# QI-01.net
KiCad netlist of a schematic drawn in EAGLE
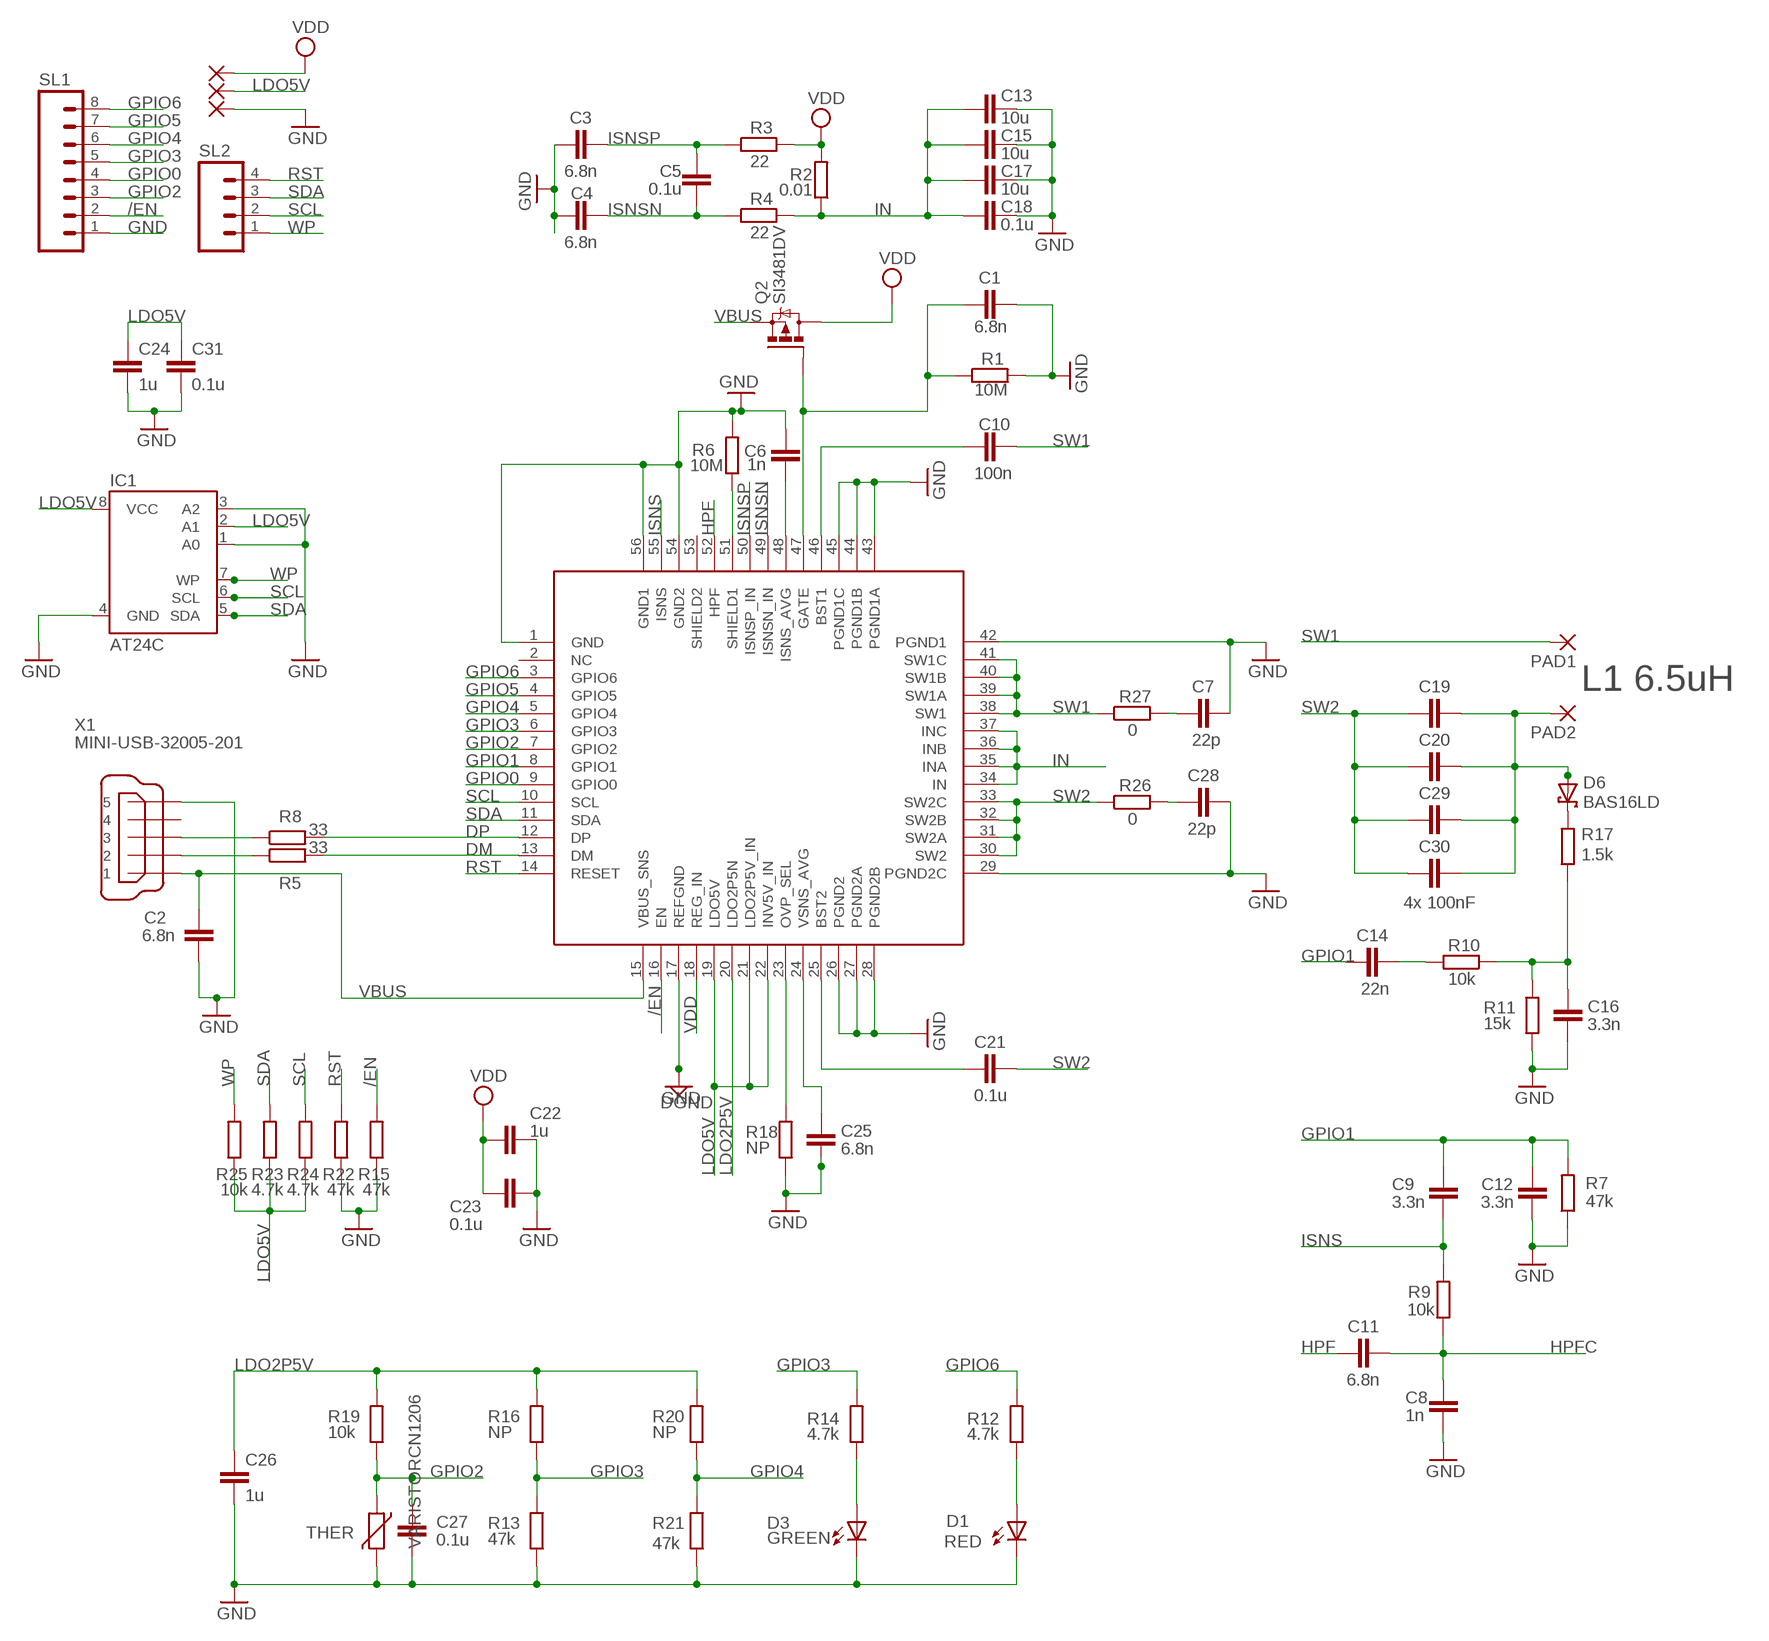
[diagram p0: schematic, sheet 1]

(export (version "E")
  (design (tool "Eeschema 10.0.6"))
  (components
    (comp (ref "C1")
      (value "6.8n")
      (footprint "eagle-import:C0402")
      (libsource (lib "eagle-import") (part "C-EUC0402"))
    )
    (comp (ref "C2")
      (value "6.8n")
      (footprint "eagle-import:C0402")
      (libsource (lib "eagle-import") (part "C-EUC0402"))
    )
    (comp (ref "C3")
      (value "6.8n")
      (footprint "eagle-import:C0402")
      (libsource (lib "eagle-import") (part "C-EUC0402"))
    )
    (comp (ref "C4")
      (value "6.8n")
      (footprint "eagle-import:C0402")
      (libsource (lib "eagle-import") (part "C-EUC0402"))
    )
    (comp (ref "C5")
      (value "0.1u")
      (footprint "eagle-import:C0402")
      (libsource (lib "eagle-import") (part "C-EUC0402"))
    )
    (comp (ref "C6")
      (value "1n")
      (footprint "eagle-import:C0402")
      (libsource (lib "eagle-import") (part "C-EUC0402"))
    )
    (comp (ref "C7")
      (value "22p")
      (footprint "eagle-import:C0402")
      (libsource (lib "eagle-import") (part "C-EUC0402"))
    )
    (comp (ref "C8")
      (value "1n")
      (footprint "eagle-import:C0402")
      (libsource (lib "eagle-import") (part "C-EUC0402"))
    )
    (comp (ref "C9")
      (value "3.3n")
      (footprint "eagle-import:C0402")
      (libsource (lib "eagle-import") (part "C-EUC0402"))
    )
    (comp (ref "C10")
      (value "100n")
      (footprint "eagle-import:C0402")
      (libsource (lib "eagle-import") (part "C-EUC0402"))
    )
    (comp (ref "C11")
      (value "6.8n")
      (footprint "eagle-import:C0402")
      (libsource (lib "eagle-import") (part "C-EUC0402"))
    )
    (comp (ref "C12")
      (value "3.3n")
      (footprint "eagle-import:C0402")
      (libsource (lib "eagle-import") (part "C-EUC0402"))
    )
    (comp (ref "C13")
      (value "10u")
      (footprint "eagle-import:C0805")
      (libsource (lib "eagle-import") (part "C-EUC0805"))
    )
    (comp (ref "C14")
      (value "22n")
      (footprint "eagle-import:C0402")
      (libsource (lib "eagle-import") (part "C-EUC0402"))
    )
    (comp (ref "C15")
      (value "10u")
      (footprint "eagle-import:C0805")
      (libsource (lib "eagle-import") (part "C-EUC0805"))
    )
    (comp (ref "C16")
      (value "3.3n")
      (footprint "eagle-import:C0402")
      (libsource (lib "eagle-import") (part "C-EUC0402"))
    )
    (comp (ref "C17")
      (value "10u")
      (footprint "eagle-import:C0805")
      (libsource (lib "eagle-import") (part "C-EUC0805"))
    )
    (comp (ref "C18")
      (value "0.1u")
      (footprint "eagle-import:C0402")
      (libsource (lib "eagle-import") (part "C-EUC0402"))
    )
    (comp (ref "C19")
      (value "100n")
      (footprint "eagle-import:C1206")
      (libsource (lib "eagle-import") (part "C-EUC1206"))
    )
    (comp (ref "C20")
      (value "100n")
      (footprint "eagle-import:C1206")
      (libsource (lib "eagle-import") (part "C-EUC1206"))
    )
    (comp (ref "C21")
      (value "0.1u")
      (footprint "eagle-import:C0402")
      (libsource (lib "eagle-import") (part "C-EUC0402"))
    )
    (comp (ref "C22")
      (value "1u")
      (footprint "eagle-import:C0402")
      (libsource (lib "eagle-import") (part "C-EUC0402"))
    )
    (comp (ref "C23")
      (value "0.1u")
      (footprint "eagle-import:C0402")
      (libsource (lib "eagle-import") (part "C-EUC0402"))
    )
    (comp (ref "C24")
      (value "1u")
      (footprint "eagle-import:C0402")
      (libsource (lib "eagle-import") (part "C-EUC0402"))
    )
    (comp (ref "C25")
      (value "6.8n")
      (footprint "eagle-import:C0402")
      (libsource (lib "eagle-import") (part "C-EUC0402"))
    )
    (comp (ref "C26")
      (value "1u")
      (footprint "eagle-import:C0402")
      (libsource (lib "eagle-import") (part "C-EUC0402"))
    )
    (comp (ref "C27")
      (value "0.1u")
      (footprint "eagle-import:C0402")
      (libsource (lib "eagle-import") (part "C-EUC0402"))
    )
    (comp (ref "C28")
      (value "22p")
      (footprint "eagle-import:C0402")
      (libsource (lib "eagle-import") (part "C-EUC0402"))
    )
    (comp (ref "C29")
      (value "100n")
      (footprint "eagle-import:C1206")
      (libsource (lib "eagle-import") (part "C-EUC1206"))
    )
    (comp (ref "C30")
      (value "100n")
      (footprint "eagle-import:C1206")
      (libsource (lib "eagle-import") (part "C-EUC1206"))
    )
    (comp (ref "C31")
      (value "0.1u")
      (footprint "eagle-import:C0402")
      (libsource (lib "eagle-import") (part "C-EUC0402"))
    )
    (comp (ref "D1")
      (value "RED")
      (footprint "eagle-import:SML0603")
      (libsource (lib "eagle-import") (part "LEDSML0603"))
    )
    (comp (ref "D3")
      (value "GREEN")
      (footprint "eagle-import:SML0603")
      (libsource (lib "eagle-import") (part "LEDSML0603"))
    )
    (comp (ref "D6")
      (value "BAS16LD")
      (footprint "eagle-import:SMB")
      (libsource (lib "eagle-import") (part "SCHOTTKY-DIODESMD"))
    )
    (comp (ref "IC1")
      (value "AT24C")
      (footprint "eagle-import:TSSOP8")
      (fields (field (name "SPICEPREFIX") "X"))
      (libsource (lib "eagle-import") (part "AT24C"))
    )
    (comp (ref "PAD1")
      (value "2,54/1,0")
      (footprint "eagle-import:2,54_1,0")
      (libsource (lib "eagle-import") (part "2,54/1,0"))
    )
    (comp (ref "PAD2")
      (value "2,54/1,0")
      (footprint "eagle-import:2,54_1,0")
      (libsource (lib "eagle-import") (part "2,54/1,0"))
    )
    (comp (ref "PAD3")
      (value "2,15/1,0")
      (footprint "eagle-import:2,15_1,0")
      (libsource (lib "eagle-import") (part "2,15/1,0"))
    )
    (comp (ref "PAD4")
      (value "2,15/1,0")
      (footprint "eagle-import:2,15_1,0")
      (libsource (lib "eagle-import") (part "2,15/1,0"))
    )
    (comp (ref "PAD5")
      (value "2,15/1,0")
      (footprint "eagle-import:2,15_1,0")
      (libsource (lib "eagle-import") (part "2,15/1,0"))
    )
    (comp (ref "Q2")
      (value "SI3481DV")
      (footprint "eagle-import:TSOP-6.PAC")
      (libsource (lib "eagle-import") (part "SI3481DV"))
    )
    (comp (ref "R1")
      (value "10M")
      (footprint "eagle-import:R0402")
      (libsource (lib "eagle-import") (part "R-EU_R0402"))
    )
    (comp (ref "R2")
      (value "0.01")
      (footprint "eagle-import:R0805")
      (libsource (lib "eagle-import") (part "R-EU_R0805"))
    )
    (comp (ref "R3")
      (value "22")
      (footprint "eagle-import:R0402")
      (libsource (lib "eagle-import") (part "R-EU_R0402"))
    )
    (comp (ref "R4")
      (value "22")
      (footprint "eagle-import:R0402")
      (libsource (lib "eagle-import") (part "R-EU_R0402"))
    )
    (comp (ref "R5")
      (value "33")
      (footprint "eagle-import:R0402")
      (libsource (lib "eagle-import") (part "R-EU_R0402"))
    )
    (comp (ref "R6")
      (value "10M")
      (footprint "eagle-import:R0402")
      (libsource (lib "eagle-import") (part "R-EU_R0402"))
    )
    (comp (ref "R7")
      (value "47k")
      (footprint "eagle-import:R0402")
      (libsource (lib "eagle-import") (part "R-EU_R0402"))
    )
    (comp (ref "R8")
      (value "33")
      (footprint "eagle-import:R0402")
      (libsource (lib "eagle-import") (part "R-EU_R0402"))
    )
    (comp (ref "R9")
      (value "10k")
      (footprint "eagle-import:R0402")
      (libsource (lib "eagle-import") (part "R-EU_R0402"))
    )
    (comp (ref "R10")
      (value "10k")
      (footprint "eagle-import:R0402")
      (libsource (lib "eagle-import") (part "R-EU_R0402"))
    )
    (comp (ref "R11")
      (value "15k")
      (footprint "eagle-import:R0402")
      (libsource (lib "eagle-import") (part "R-EU_R0402"))
    )
    (comp (ref "R12")
      (value "4.7k")
      (footprint "eagle-import:R0402")
      (libsource (lib "eagle-import") (part "R-EU_R0402"))
    )
    (comp (ref "R13")
      (value "47k")
      (footprint "eagle-import:R0603")
      (libsource (lib "eagle-import") (part "R-EU_R0603"))
    )
    (comp (ref "R14")
      (value "4.7k")
      (footprint "eagle-import:R0402")
      (libsource (lib "eagle-import") (part "R-EU_R0402"))
    )
    (comp (ref "R15")
      (value "47k")
      (footprint "eagle-import:R0603")
      (libsource (lib "eagle-import") (part "R-EU_R0603"))
    )
    (comp (ref "R16")
      (value "NP")
      (footprint "eagle-import:R0402")
      (libsource (lib "eagle-import") (part "R-EU_R0402"))
    )
    (comp (ref "R17")
      (value "1.5k")
      (footprint "eagle-import:R0402")
      (libsource (lib "eagle-import") (part "R-EU_R0402"))
    )
    (comp (ref "R18")
      (value "NP")
      (footprint "eagle-import:R0402")
      (libsource (lib "eagle-import") (part "R-EU_R0402"))
    )
    (comp (ref "R19")
      (value "10k")
      (footprint "eagle-import:R0402")
      (libsource (lib "eagle-import") (part "R-EU_R0402"))
    )
    (comp (ref "R20")
      (value "NP")
      (footprint "eagle-import:R0402")
      (libsource (lib "eagle-import") (part "R-EU_R0402"))
    )
    (comp (ref "R21")
      (value "47k")
      (footprint "eagle-import:R0603")
      (libsource (lib "eagle-import") (part "R-EU_R0603"))
    )
    (comp (ref "R22")
      (value "47k")
      (footprint "eagle-import:R0603")
      (libsource (lib "eagle-import") (part "R-EU_R0603"))
    )
    (comp (ref "R23")
      (value "4.7k")
      (footprint "eagle-import:R0402")
      (libsource (lib "eagle-import") (part "R-EU_R0402"))
    )
    (comp (ref "R24")
      (value "4.7k")
      (footprint "eagle-import:R0402")
      (libsource (lib "eagle-import") (part "R-EU_R0402"))
    )
    (comp (ref "R25")
      (value "10k")
      (footprint "eagle-import:R0402")
      (libsource (lib "eagle-import") (part "R-EU_R0402"))
    )
    (comp (ref "R26")
      (value "0")
      (footprint "eagle-import:R0402")
      (libsource (lib "eagle-import") (part "R-EU_R0402"))
    )
    (comp (ref "R27")
      (value "0")
      (footprint "eagle-import:R0402")
      (libsource (lib "eagle-import") (part "R-EU_R0402"))
    )
    (comp (ref "SL1")
      (value "M08")
      (footprint "eagle-import:08P")
      (libsource (lib "eagle-import") (part "M08"))
    )
    (comp (ref "SL2")
      (value "M04")
      (footprint "eagle-import:04P")
      (libsource (lib "eagle-import") (part "M04"))
    )
    (comp (ref "THER")
      (value "VARISTORCN1206")
      (footprint "eagle-import:CT_CN1206")
      (libsource (lib "eagle-import") (part "VARISTORCN1206"))
    )
    (comp (ref "U$1")
      (value "VFQFPN")
      (footprint "eagle-import:ZADANIE")
      (libsource (lib "eagle-import") (part "VFQFPN"))
    )
    (comp (ref "X1")
      (value "MINI-USB-32005-201")
      (footprint "eagle-import:32005-201")
      (libsource (lib "eagle-import") (part "MINI-USB-32005-201"))
    )
  )
  (nets
    (net (code "1") (name "/DM") (class "Default")
      (node (ref "R5") (pin "2") (pinfunction "2_2") (pintype "passive"))
      (node (ref "U$1") (pin "13") (pinfunction "DM_13") (pintype "bidirectional"))
    )
    (net (code "2") (name "/DP") (class "Default")
      (node (ref "R8") (pin "2") (pinfunction "2_2") (pintype "passive"))
      (node (ref "U$1") (pin "12") (pinfunction "DP_12") (pintype "bidirectional"))
    )
    (net (code "3") (name "/GPIO0") (class "Default")
      (node (ref "SL1") (pin "4") (pinfunction "4_4") (pintype "passive"))
      (node (ref "U$1") (pin "9") (pinfunction "GPIO0_9") (pintype "bidirectional"))
    )
    (net (code "4") (name "/GPIO1") (class "Default")
      (node (ref "C12") (pin "2") (pinfunction "2_2") (pintype "passive"))
      (node (ref "C14") (pin "1") (pinfunction "1_1") (pintype "passive"))
      (node (ref "C9") (pin "2") (pinfunction "2_2") (pintype "passive"))
      (node (ref "R7") (pin "2") (pinfunction "2_2") (pintype "passive"))
      (node (ref "U$1") (pin "8") (pinfunction "GPIO1_8") (pintype "bidirectional"))
    )
    (net (code "5") (name "/GPIO2") (class "Default")
      (node (ref "C27") (pin "1") (pinfunction "1_1") (pintype "passive"))
      (node (ref "R19") (pin "1") (pinfunction "1_1") (pintype "passive"))
      (node (ref "SL1") (pin "3") (pinfunction "3_3") (pintype "passive"))
      (node (ref "THER") (pin "1") (pinfunction "1_1") (pintype "passive"))
      (node (ref "U$1") (pin "7") (pinfunction "GPIO2_7") (pintype "bidirectional"))
    )
    (net (code "6") (name "/GPIO3") (class "Default")
      (node (ref "R13") (pin "2") (pinfunction "2_2") (pintype "passive"))
      (node (ref "R14") (pin "2") (pinfunction "2_2") (pintype "passive"))
      (node (ref "R16") (pin "1") (pinfunction "1_1") (pintype "passive"))
      (node (ref "SL1") (pin "5") (pinfunction "5_5") (pintype "passive"))
      (node (ref "U$1") (pin "6") (pinfunction "GPIO3_6") (pintype "bidirectional"))
    )
    (net (code "7") (name "/GPIO4") (class "Default")
      (node (ref "R20") (pin "1") (pinfunction "1_1") (pintype "passive"))
      (node (ref "R21") (pin "2") (pinfunction "2_2") (pintype "passive"))
      (node (ref "SL1") (pin "6") (pinfunction "6_6") (pintype "passive"))
      (node (ref "U$1") (pin "5") (pinfunction "GPIO4_5") (pintype "bidirectional"))
    )
    (net (code "8") (name "/GPIO5") (class "Default")
      (node (ref "SL1") (pin "7") (pinfunction "7_7") (pintype "passive"))
      (node (ref "U$1") (pin "4") (pinfunction "GPIO5_4") (pintype "bidirectional"))
    )
    (net (code "9") (name "/GPIO6") (class "Default")
      (node (ref "R12") (pin "2") (pinfunction "2_2") (pintype "passive"))
      (node (ref "SL1") (pin "8") (pinfunction "8_8") (pintype "passive"))
      (node (ref "U$1") (pin "3") (pinfunction "GPIO6_3") (pintype "bidirectional"))
    )
    (net (code "10") (name "/HPF") (class "Default")
      (node (ref "C11") (pin "1") (pinfunction "1_1") (pintype "passive"))
      (node (ref "U$1") (pin "52") (pinfunction "HPF_52") (pintype "bidirectional"))
    )
    (net (code "11") (name "/HPFC") (class "Default")
      (node (ref "C11") (pin "2") (pinfunction "2_2") (pintype "passive"))
      (node (ref "C8") (pin "2") (pinfunction "2_2") (pintype "passive"))
      (node (ref "R9") (pin "1") (pinfunction "1_1") (pintype "passive"))
    )
    (net (code "12") (name "/IN") (class "Default")
      (node (ref "C13") (pin "2") (pinfunction "2_2") (pintype "passive"))
      (node (ref "C15") (pin "2") (pinfunction "2_2") (pintype "passive"))
      (node (ref "C17") (pin "2") (pinfunction "2_2") (pintype "passive"))
      (node (ref "C18") (pin "2") (pinfunction "2_2") (pintype "passive"))
      (node (ref "R2") (pin "1") (pinfunction "1_1") (pintype "passive"))
      (node (ref "R4") (pin "2") (pinfunction "2_2") (pintype "passive"))
      (node (ref "U$1") (pin "34") (pinfunction "IN_34") (pintype "bidirectional"))
      (node (ref "U$1") (pin "35") (pinfunction "INA_35") (pintype "bidirectional"))
      (node (ref "U$1") (pin "36") (pinfunction "INB_36") (pintype "bidirectional"))
      (node (ref "U$1") (pin "37") (pinfunction "INC_37") (pintype "bidirectional"))
    )
    (net (code "13") (name "/ISNS") (class "Default")
      (node (ref "C9") (pin "1") (pinfunction "1_1") (pintype "passive"))
      (node (ref "R9") (pin "2") (pinfunction "2_2") (pintype "passive"))
      (node (ref "U$1") (pin "55") (pinfunction "ISNS_55") (pintype "bidirectional"))
    )
    (net (code "14") (name "/ISNSN") (class "Default")
      (node (ref "C4") (pin "2") (pinfunction "2_2") (pintype "passive"))
      (node (ref "C5") (pin "1") (pinfunction "1_1") (pintype "passive"))
      (node (ref "R4") (pin "1") (pinfunction "1_1") (pintype "passive"))
      (node (ref "U$1") (pin "49") (pinfunction "ISNSN_IN_49") (pintype "bidirectional"))
    )
    (net (code "15") (name "/ISNSP") (class "Default")
      (node (ref "C3") (pin "2") (pinfunction "2_2") (pintype "passive"))
      (node (ref "C5") (pin "2") (pinfunction "2_2") (pintype "passive"))
      (node (ref "R3") (pin "1") (pinfunction "1_1") (pintype "passive"))
      (node (ref "U$1") (pin "50") (pinfunction "ISNSP_IN_50") (pintype "bidirectional"))
    )
    (net (code "16") (name "/LDO2P5V") (class "Default")
      (node (ref "C26") (pin "1") (pinfunction "1_1") (pintype "passive"))
      (node (ref "R16") (pin "2") (pinfunction "2_2") (pintype "passive"))
      (node (ref "R19") (pin "2") (pinfunction "2_2") (pintype "passive"))
      (node (ref "R20") (pin "2") (pinfunction "2_2") (pintype "passive"))
      (node (ref "U$1") (pin "20") (pinfunction "LDO2P5N_20") (pintype "bidirectional"))
    )
    (net (code "17") (name "/LDO5V") (class "Default")
      (node (ref "C24") (pin "1") (pinfunction "1_1") (pintype "passive"))
      (node (ref "C31") (pin "1") (pinfunction "1_1") (pintype "passive"))
      (node (ref "IC1") (pin "2") (pinfunction "A1_2") (pintype "input"))
      (node (ref "IC1") (pin "8") (pinfunction "VCC_8") (pintype "power_in"))
      (node (ref "PAD4") (pin "1") (pinfunction "P_1") (pintype "passive"))
      (node (ref "R23") (pin "1") (pinfunction "1_1") (pintype "passive"))
      (node (ref "R24") (pin "1") (pinfunction "1_1") (pintype "passive"))
      (node (ref "R25") (pin "1") (pinfunction "1_1") (pintype "passive"))
      (node (ref "U$1") (pin "19") (pinfunction "LDO5V_19") (pintype "bidirectional"))
      (node (ref "U$1") (pin "21") (pinfunction "LDO2P5V_IN_21") (pintype "bidirectional"))
      (node (ref "U$1") (pin "22") (pinfunction "INV5V_IN_22") (pintype "bidirectional"))
    )
    (net (code "18") (name "/RST") (class "Default")
      (node (ref "R22") (pin "2") (pinfunction "2_2") (pintype "passive"))
      (node (ref "SL2") (pin "4") (pinfunction "4_4") (pintype "passive"))
      (node (ref "U$1") (pin "14") (pinfunction "RESET_14") (pintype "bidirectional"))
    )
    (net (code "19") (name "/SCL") (class "Default")
      (node (ref "IC1") (pin "6") (pinfunction "SCL_6") (pintype "bidirectional"))
      (node (ref "R24") (pin "2") (pinfunction "2_2") (pintype "passive"))
      (node (ref "SL2") (pin "2") (pinfunction "2_2") (pintype "passive"))
      (node (ref "U$1") (pin "10") (pinfunction "SCL_10") (pintype "bidirectional"))
    )
    (net (code "20") (name "/SDA") (class "Default")
      (node (ref "IC1") (pin "5") (pinfunction "SDA_5") (pintype "bidirectional"))
      (node (ref "R23") (pin "2") (pinfunction "2_2") (pintype "passive"))
      (node (ref "SL2") (pin "3") (pinfunction "3_3") (pintype "passive"))
      (node (ref "U$1") (pin "11") (pinfunction "SDA_11") (pintype "bidirectional"))
    )
    (net (code "21") (name "/SW1") (class "Default")
      (node (ref "C10") (pin "1") (pinfunction "1_1") (pintype "passive"))
      (node (ref "PAD1") (pin "1") (pinfunction "P_1") (pintype "passive"))
      (node (ref "R27") (pin "1") (pinfunction "1_1") (pintype "passive"))
      (node (ref "U$1") (pin "38") (pinfunction "SW1_38") (pintype "bidirectional"))
      (node (ref "U$1") (pin "39") (pinfunction "SW1A_39") (pintype "bidirectional"))
      (node (ref "U$1") (pin "40") (pinfunction "SW1B_40") (pintype "bidirectional"))
      (node (ref "U$1") (pin "41") (pinfunction "SW1C_41") (pintype "bidirectional"))
    )
    (net (code "22") (name "/SW2") (class "Default")
      (node (ref "C19") (pin "2") (pinfunction "2_2") (pintype "passive"))
      (node (ref "C20") (pin "2") (pinfunction "2_2") (pintype "passive"))
      (node (ref "C21") (pin "1") (pinfunction "1_1") (pintype "passive"))
      (node (ref "C29") (pin "2") (pinfunction "2_2") (pintype "passive"))
      (node (ref "C30") (pin "2") (pinfunction "2_2") (pintype "passive"))
      (node (ref "R26") (pin "1") (pinfunction "1_1") (pintype "passive"))
      (node (ref "U$1") (pin "30") (pinfunction "SW2_30") (pintype "bidirectional"))
      (node (ref "U$1") (pin "31") (pinfunction "SW2A_31") (pintype "bidirectional"))
      (node (ref "U$1") (pin "32") (pinfunction "SW2B_32") (pintype "bidirectional"))
      (node (ref "U$1") (pin "33") (pinfunction "SW2C_33") (pintype "bidirectional"))
    )
    (net (code "23") (name "/VBUS") (class "Default")
      (node (ref "C2") (pin "2") (pinfunction "2_2") (pintype "passive"))
      (node (ref "Q2") (pin "4") (pinfunction "S_4") (pintype "passive"))
      (node (ref "U$1") (pin "15") (pinfunction "VBUS_SNS_15") (pintype "bidirectional"))
      (node (ref "X1") (pin "1") (pinfunction "1_1") (pintype "passive"))
    )
    (net (code "24") (name "/WP") (class "Default")
      (node (ref "IC1") (pin "7") (pinfunction "WP_7") (pintype "input"))
      (node (ref "R25") (pin "2") (pinfunction "2_2") (pintype "passive"))
      (node (ref "SL2") (pin "1") (pinfunction "1_1") (pintype "passive"))
    )
    (net (code "25") (name "/{slash}EN") (class "Default")
      (node (ref "R15") (pin "2") (pinfunction "2_2") (pintype "passive"))
      (node (ref "SL1") (pin "2") (pinfunction "2_2") (pintype "passive"))
      (node (ref "U$1") (pin "16") (pinfunction "EN_16") (pintype "bidirectional"))
    )
    (net (code "26") (name "DGND") (class "Default")
      (node (ref "C1") (pin "1") (pinfunction "1_1") (pintype "passive"))
      (node (ref "C12") (pin "1") (pinfunction "1_1") (pintype "passive"))
      (node (ref "C13") (pin "1") (pinfunction "1_1") (pintype "passive"))
      (node (ref "C15") (pin "1") (pinfunction "1_1") (pintype "passive"))
      (node (ref "C16") (pin "2") (pinfunction "2_2") (pintype "passive"))
      (node (ref "C17") (pin "1") (pinfunction "1_1") (pintype "passive"))
      (node (ref "C18") (pin "1") (pinfunction "1_1") (pintype "passive"))
      (node (ref "C2") (pin "1") (pinfunction "1_1") (pintype "passive"))
      (node (ref "C22") (pin "1") (pinfunction "1_1") (pintype "passive"))
      (node (ref "C23") (pin "1") (pinfunction "1_1") (pintype "passive"))
      (node (ref "C24") (pin "2") (pinfunction "2_2") (pintype "passive"))
      (node (ref "C25") (pin "2") (pinfunction "2_2") (pintype "passive"))
      (node (ref "C26") (pin "2") (pinfunction "2_2") (pintype "passive"))
      (node (ref "C27") (pin "2") (pinfunction "2_2") (pintype "passive"))
      (node (ref "C28") (pin "1") (pinfunction "1_1") (pintype "passive"))
      (node (ref "C3") (pin "1") (pinfunction "1_1") (pintype "passive"))
      (node (ref "C31") (pin "2") (pinfunction "2_2") (pintype "passive"))
      (node (ref "C4") (pin "1") (pinfunction "1_1") (pintype "passive"))
      (node (ref "C6") (pin "1") (pinfunction "1_1") (pintype "passive"))
      (node (ref "C7") (pin "1") (pinfunction "1_1") (pintype "passive"))
      (node (ref "C8") (pin "1") (pinfunction "1_1") (pintype "passive"))
      (node (ref "D1") (pin "C") (pinfunction "C_C") (pintype "passive"))
      (node (ref "D3") (pin "C") (pinfunction "C_C") (pintype "passive"))
      (node (ref "IC1") (pin "1") (pinfunction "A0_1") (pintype "input"))
      (node (ref "IC1") (pin "3") (pinfunction "A2_3") (pintype "input"))
      (node (ref "IC1") (pin "4") (pinfunction "GND_4") (pintype "power_in"))
      (node (ref "PAD5") (pin "1") (pinfunction "P_1") (pintype "passive"))
      (node (ref "R1") (pin "2") (pinfunction "2_2") (pintype "passive"))
      (node (ref "R11") (pin "1") (pinfunction "1_1") (pintype "passive"))
      (node (ref "R13") (pin "1") (pinfunction "1_1") (pintype "passive"))
      (node (ref "R15") (pin "1") (pinfunction "1_1") (pintype "passive"))
      (node (ref "R18") (pin "1") (pinfunction "1_1") (pintype "passive"))
      (node (ref "R21") (pin "1") (pinfunction "1_1") (pintype "passive"))
      (node (ref "R22") (pin "1") (pinfunction "1_1") (pintype "passive"))
      (node (ref "R6") (pin "2") (pinfunction "2_2") (pintype "passive"))
      (node (ref "R7") (pin "1") (pinfunction "1_1") (pintype "passive"))
      (node (ref "SL1") (pin "1") (pinfunction "1_1") (pintype "passive"))
      (node (ref "THER") (pin "2") (pinfunction "2_2") (pintype "passive"))
      (node (ref "U$1") (pin "1") (pinfunction "GND_1") (pintype "bidirectional"))
      (node (ref "U$1") (pin "17") (pinfunction "REFGND_17") (pintype "bidirectional"))
      (node (ref "U$1") (pin "26") (pinfunction "PGND2_26") (pintype "bidirectional"))
      (node (ref "U$1") (pin "27") (pinfunction "PGND2A_27") (pintype "bidirectional"))
      (node (ref "U$1") (pin "28") (pinfunction "PGND2B_28") (pintype "bidirectional"))
      (node (ref "U$1") (pin "29") (pinfunction "PGND2C_29") (pintype "bidirectional"))
      (node (ref "U$1") (pin "42") (pinfunction "PGND1_42") (pintype "bidirectional"))
      (node (ref "U$1") (pin "43") (pinfunction "PGND1A_43") (pintype "bidirectional"))
      (node (ref "U$1") (pin "44") (pinfunction "PGND1B_44") (pintype "bidirectional"))
      (node (ref "U$1") (pin "45") (pinfunction "PGND1C_45") (pintype "bidirectional"))
      (node (ref "U$1") (pin "54") (pinfunction "GND2_54") (pintype "bidirectional"))
      (node (ref "U$1") (pin "56") (pinfunction "GND1_56") (pintype "bidirectional"))
      (node (ref "X1") (pin "5") (pinfunction "5_5") (pintype "passive"))
    )
    (net (code "27") (name "Net-(C7-Pad2)") (class "Default")
      (node (ref "C7") (pin "2") (pinfunction "2_2") (pintype "passive"))
      (node (ref "R27") (pin "2") (pinfunction "2_2") (pintype "passive"))
    )
    (net (code "28") (name "Net-(C14-Pad2)") (class "Default")
      (node (ref "C14") (pin "2") (pinfunction "2_2") (pintype "passive"))
      (node (ref "R10") (pin "2") (pinfunction "2_2") (pintype "passive"))
    )
    (net (code "29") (name "Net-(C16-Pad1)") (class "Default")
      (node (ref "C16") (pin "1") (pinfunction "1_1") (pintype "passive"))
      (node (ref "R10") (pin "1") (pinfunction "1_1") (pintype "passive"))
      (node (ref "R11") (pin "2") (pinfunction "2_2") (pintype "passive"))
      (node (ref "R17") (pin "1") (pinfunction "1_1") (pintype "passive"))
    )
    (net (code "30") (name "Net-(C28-Pad2)") (class "Default")
      (node (ref "C28") (pin "2") (pinfunction "2_2") (pintype "passive"))
      (node (ref "R26") (pin "2") (pinfunction "2_2") (pintype "passive"))
    )
    (net (code "31") (name "Net-(D1-PadA)") (class "Default")
      (node (ref "D1") (pin "A") (pinfunction "A_A") (pintype "passive"))
      (node (ref "R12") (pin "1") (pinfunction "1_1") (pintype "passive"))
    )
    (net (code "32") (name "Net-(D3-PadA)") (class "Default")
      (node (ref "D3") (pin "A") (pinfunction "A_A") (pintype "passive"))
      (node (ref "R14") (pin "1") (pinfunction "1_1") (pintype "passive"))
    )
    (net (code "33") (name "Net-(D6-PadC)") (class "Default")
      (node (ref "D6") (pin "C") (pinfunction "C_C") (pintype "passive"))
      (node (ref "R17") (pin "2") (pinfunction "2_2") (pintype "passive"))
    )
    (net (code "34") (name "Net-(PAD2-P)") (class "Default")
      (node (ref "C19") (pin "1") (pinfunction "1_1") (pintype "passive"))
      (node (ref "C20") (pin "1") (pinfunction "1_1") (pintype "passive"))
      (node (ref "C29") (pin "1") (pinfunction "1_1") (pintype "passive"))
      (node (ref "C30") (pin "1") (pinfunction "1_1") (pintype "passive"))
      (node (ref "D6") (pin "A") (pinfunction "A_A") (pintype "passive"))
      (node (ref "PAD2") (pin "1") (pinfunction "P_1") (pintype "passive"))
    )
    (net (code "35") (name "Net-(Q2-G)") (class "Default")
      (node (ref "C1") (pin "2") (pinfunction "2_2") (pintype "passive"))
      (node (ref "Q2") (pin "3") (pinfunction "G_3") (pintype "passive"))
      (node (ref "R1") (pin "1") (pinfunction "1_1") (pintype "passive"))
      (node (ref "U$1") (pin "47") (pinfunction "GATE_47") (pintype "bidirectional"))
    )
    (net (code "36") (name "Net-(R5-Pad1)") (class "Default")
      (node (ref "R5") (pin "1") (pinfunction "1_1") (pintype "passive"))
      (node (ref "X1") (pin "2") (pinfunction "2_2") (pintype "passive"))
    )
    (net (code "37") (name "Net-(R8-Pad1)") (class "Default")
      (node (ref "R8") (pin "1") (pinfunction "1_1") (pintype "passive"))
      (node (ref "X1") (pin "3") (pinfunction "3_3") (pintype "passive"))
    )
    (net (code "38") (name "Net-(U$1-BST1)") (class "Default")
      (node (ref "C10") (pin "2") (pinfunction "2_2") (pintype "passive"))
      (node (ref "U$1") (pin "46") (pinfunction "BST1_46") (pintype "bidirectional"))
    )
    (net (code "39") (name "Net-(U$1-BST2)") (class "Default")
      (node (ref "C21") (pin "2") (pinfunction "2_2") (pintype "passive"))
      (node (ref "U$1") (pin "25") (pinfunction "BST2_25") (pintype "bidirectional"))
    )
    (net (code "40") (name "Net-(U$1-ISNS_AVG)") (class "Default")
      (node (ref "C6") (pin "2") (pinfunction "2_2") (pintype "passive"))
      (node (ref "U$1") (pin "48") (pinfunction "ISNS_AVG_48") (pintype "bidirectional"))
    )
    (net (code "41") (name "Net-(U$1-OVP_SEL)") (class "Default")
      (node (ref "R18") (pin "2") (pinfunction "2_2") (pintype "passive"))
      (node (ref "U$1") (pin "23") (pinfunction "OVP_SEL_23") (pintype "bidirectional"))
    )
    (net (code "42") (name "Net-(U$1-SHIELD1)") (class "Default")
      (node (ref "R6") (pin "1") (pinfunction "1_1") (pintype "passive"))
      (node (ref "U$1") (pin "51") (pinfunction "SHIELD1_51") (pintype "bidirectional"))
    )
    (net (code "43") (name "Net-(U$1-VSNS_AVG)") (class "Default")
      (node (ref "C25") (pin "1") (pinfunction "1_1") (pintype "passive"))
      (node (ref "U$1") (pin "24") (pinfunction "VSNS_AVG_24") (pintype "bidirectional"))
    )
    (net (code "44") (name "VDD") (class "Default")
      (node (ref "C22") (pin "2") (pinfunction "2_2") (pintype "passive"))
      (node (ref "C23") (pin "2") (pinfunction "2_2") (pintype "passive"))
      (node (ref "PAD3") (pin "1") (pinfunction "P_1") (pintype "passive"))
      (node (ref "Q2") (pin "1") (pinfunction "D_1") (pintype "passive"))
      (node (ref "Q2") (pin "2") (pinfunction "D_2") (pintype "passive"))
      (node (ref "Q2") (pin "5") (pinfunction "D_5") (pintype "passive"))
      (node (ref "Q2") (pin "6") (pinfunction "D_6") (pintype "passive"))
      (node (ref "R2") (pin "2") (pinfunction "2_2") (pintype "passive"))
      (node (ref "R3") (pin "2") (pinfunction "2_2") (pintype "passive"))
      (node (ref "U$1") (pin "18") (pinfunction "REG_IN_18") (pintype "bidirectional"))
    )
    (net (code "45") (name "unconnected-(U$1-NC-Pad2)") (class "Default")
      (node (ref "U$1") (pin "2") (pinfunction "NC_2") (pintype "bidirectional"))
    )
    (net (code "46") (name "unconnected-(U$1-SHIELD2-Pad53)") (class "Default")
      (node (ref "U$1") (pin "53") (pinfunction "SHIELD2_53") (pintype "bidirectional"))
    )
    (net (code "47") (name "unconnected-(X1-Pad4)") (class "Default")
      (node (ref "X1") (pin "4") (pinfunction "4_4") (pintype "passive"))
    )
  )
)
